# NNLightSwitcher_connectors.net
KiCad netlist of a schematic drawn in Altium Designer
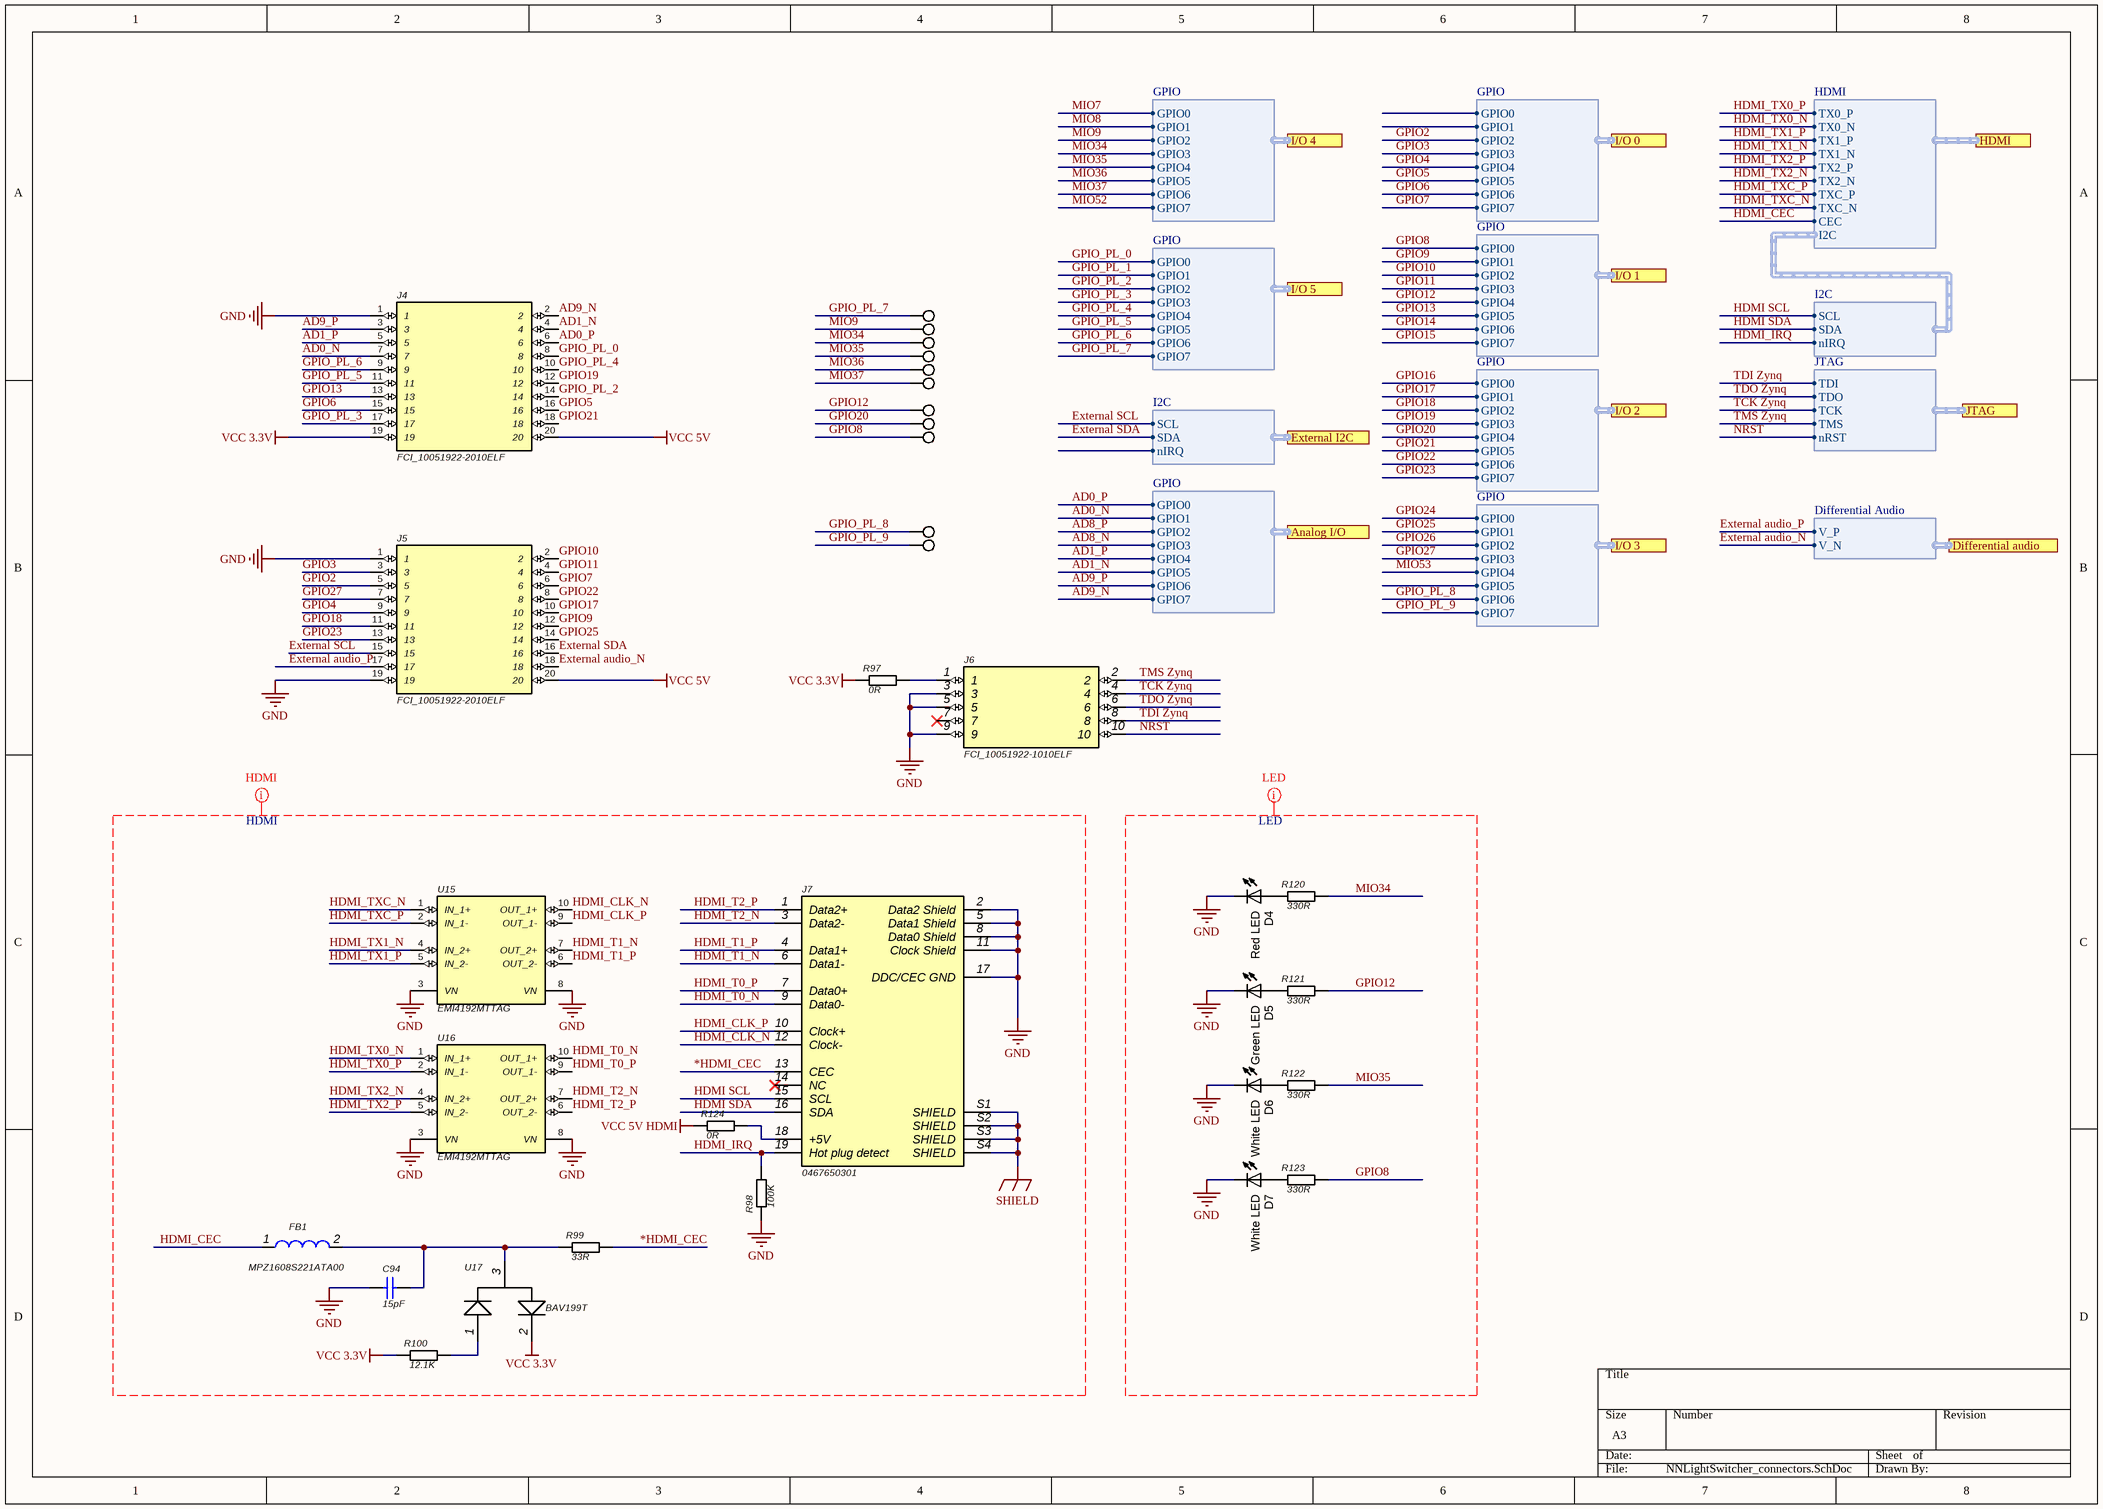
[diagram p0: NNLightSwitcher_connectors.SchDoc]

(export (version "E")
  (design (tool "Eeschema 10.0.6"))
  (components
    (comp (ref "C94")
      (value "15pF")
      (footprint "0402")
      (libsource (lib "NNLightSwitcher") (part "Capacitor 15pF"))
    )
    (comp (ref "D4")
      (value "Red LED")
      (footprint "*LED_SML-P11UTT86R_SML-P11MTT86(Primary)")
      (description "LED red 0402")
      (libsource (lib "NNLightSwitcher") (part "APHHS1005SURCK"))
    )
    (comp (ref "D5")
      (value "Green LED")
      (footprint "*LED_SML-P11UTT86R_SML-P11MTT86(Primary)")
      (description "LED Uni-Color Green 525nm 2-Pin Chip 0402_1006Metric_ T/RLT_VH9G-Q2OO-25-1")
      (libsource (lib "NNLightSwitcher") (part "LT_VH9G-Q2OO-25-1"))
    )
    (comp (ref "D6")
      (value "White LED")
      (footprint "*LED_SML-P11UTT86R_SML-P11MTT86(Primary)")
      (description "LED red 0402\r\nAPG1005RWF-T-5MAV")
      (libsource (lib "NNLightSwitcher") (part "APG1005RWF-T-5MAV"))
    )
    (comp (ref "D7")
      (value "White LED")
      (footprint "*LED_SML-P11UTT86R_SML-P11MTT86(Primary)")
      (description "LED red 0402\r\nAPG1005RWF-T-5MAV")
      (libsource (lib "NNLightSwitcher") (part "APG1005RWF-T-5MAV"))
    )
    (comp (ref "FB1")
      (value "MPZ1608S221ATA00")
      (footprint "*0603")
      (description "Ferrite Bead Multi-Layer 220Ohm 25% 100MHz Ferrite 2.2A 0603 Punched Paper T/R")
      (fields (field (name "TOLERANCE") "25%"))
      (libsource (lib "NNLightSwitcher") (part "MPZ1608S221ATA00"))
    )
    (comp (ref "J4")
      (value "FCI_10051922-2010ELF")
      (footprint "*FCI_10051922-2010ELF")
      (description "0.50mm FFC/FPC Connectors 20CKT RA SMT ZIF CON BOTTOM CONTACT")
      (libsource (lib "NNLightSwitcher") (part "FCI_10051922-2010ELF"))
    )
    (comp (ref "J5")
      (value "FCI_10051922-2010ELF")
      (footprint "*FCI_10051922-2010ELF")
      (description "0.50mm FFC/FPC Connectors 20CKT RA SMT ZIF CON BOTTOM CONTACT")
      (libsource (lib "NNLightSwitcher") (part "FCI_10051922-2010ELF"))
    )
    (comp (ref "J6")
      (value "FCI_10051922-1010ELF")
      (footprint "*FCI_10051922-1010ELF")
      (description "0.50mm FFC/FPC Connectors 10CKT RA SMT ZIF CON BOTTOM CONTACT")
      (libsource (lib "NNLightSwitcher") (part "FCI_10051922-1010ELF"))
    )
    (comp (ref "J7")
      (value "0467650301")
      (footprint "MOLEX_0467650301_0467650301(Primary)")
      (description "Conn Micro HDMI RCP 19 POS 0.4mm Solder RA SMD 19 Terminal 1 Port Micro HDMI Embossed T/R")
      (libsource (lib "NNLightSwitcher") (part "Micro HDMI"))
    )
    (comp (ref "R97")
      (value "0R")
      (footprint "0402")
      (libsource (lib "NNLightSwitcher") (part "Resistor 0R"))
    )
    (comp (ref "R98")
      (value "100K")
      (footprint "0402")
      (libsource (lib "NNLightSwitcher") (part "Resistor 100K"))
    )
    (comp (ref "R99")
      (value "33R")
      (footprint "0402")
      (libsource (lib "NNLightSwitcher") (part "Resistor 33R"))
    )
    (comp (ref "R100")
      (value "12.1K")
      (footprint "0402")
      (libsource (lib "NNLightSwitcher") (part "Resistor 12.1K"))
    )
    (comp (ref "R120")
      (value "330R")
      (footprint "0402")
      (libsource (lib "NNLightSwitcher") (part "Resistor 330R"))
    )
    (comp (ref "R121")
      (value "330R")
      (footprint "0402")
      (libsource (lib "NNLightSwitcher") (part "Resistor 330R"))
    )
    (comp (ref "R122")
      (value "330R")
      (footprint "0402")
      (libsource (lib "NNLightSwitcher") (part "Resistor 330R"))
    )
    (comp (ref "R123")
      (value "330R")
      (footprint "0402")
      (libsource (lib "NNLightSwitcher") (part "Resistor 330R"))
    )
    (comp (ref "R124")
      (value "0R")
      (footprint "0402")
      (libsource (lib "NNLightSwitcher") (part "Resistor 0R"))
    )
    (comp (ref "TP50")
      (value "Test point")
      (footprint "Testpoint_with_pad")
      (description "Test Point, Miniature, SMT")
      (libsource (lib "NNLightSwitcher") (part "Test point"))
    )
    (comp (ref "TP51")
      (value "Test point")
      (footprint "Testpoint_Keystone_Miniature")
      (description "Test Point, Miniature, SMT")
      (libsource (lib "NNLightSwitcher") (part "Test point"))
    )
    (comp (ref "TP52")
      (value "Test point")
      (footprint "Testpoint_Keystone_Miniature")
      (description "Test Point, Miniature, SMT")
      (libsource (lib "NNLightSwitcher") (part "Test point"))
    )
    (comp (ref "TP53")
      (value "Test point")
      (footprint "Testpoint_Keystone_Miniature")
      (description "Test Point, Miniature, SMT")
      (libsource (lib "NNLightSwitcher") (part "Test point"))
    )
    (comp (ref "TP54")
      (value "Test point")
      (footprint "Testpoint_Keystone_Miniature")
      (description "Test Point, Miniature, SMT")
      (libsource (lib "NNLightSwitcher") (part "Test point"))
    )
    (comp (ref "TP55")
      (value "Test point")
      (footprint "Testpoint_Keystone_Miniature")
      (description "Test Point, Miniature, SMT")
      (libsource (lib "NNLightSwitcher") (part "Test point"))
    )
    (comp (ref "TP63")
      (value "Test point")
      (footprint "Testpoint_with_pad")
      (description "Test Point, Miniature, SMT")
      (libsource (lib "NNLightSwitcher") (part "Test point"))
    )
    (comp (ref "TP64")
      (value "Test point")
      (footprint "Testpoint_with_pad")
      (description "Test Point, Miniature, SMT")
      (libsource (lib "NNLightSwitcher") (part "Test point"))
    )
    (comp (ref "TP65")
      (value "Test point")
      (footprint "Testpoint_with_pad")
      (description "Test Point, Miniature, SMT")
      (libsource (lib "NNLightSwitcher") (part "Test point"))
    )
    (comp (ref "TP67")
      (value "Test point")
      (footprint "Testpoint_with_pad")
      (description "Test Point, Miniature, SMT")
      (libsource (lib "NNLightSwitcher") (part "Test point"))
    )
    (comp (ref "TP70")
      (value "Test point")
      (footprint "Testpoint_with_pad")
      (description "Test Point, Miniature, SMT")
      (libsource (lib "NNLightSwitcher") (part "Test point"))
    )
    (comp (ref "U15")
      (value "EMI4192MTTAG")
      (footprint "ONSC-WDFN-10-511BM-01_V")
      (description "Common Mode Filter with ESD Protection, -40 to 85 degC, 10-Pin WDFN, Pb-Free, Tape and Reel")
      (libsource (lib "NNLightSwitcher") (part "EMI4192MTTAG"))
    )
    (comp (ref "U16")
      (value "EMI4192MTTAG")
      (footprint "ONSC-WDFN-10-511BM-01_V")
      (description "Common Mode Filter with ESD Protection, -40 to 85 degC, 10-Pin WDFN, Pb-Free, Tape and Reel")
      (libsource (lib "NNLightSwitcher") (part "EMI4192MTTAG"))
    )
    (comp (ref "U17")
      (value "BAV199T")
      (footprint "*SOT95P240X110-3N")
      (fields (field (name "MF") "Micro Commercial"))
      (libsource (lib "NNLightSwitcher") (part "BAV199T"))
    )
  )
  (nets
    (net (code "7") (name "/*HDMI_CEC") (class "Default")
      (node (ref "J7") (pin "13") (pinfunction "CEC_13") (pintype "passive"))
      (node (ref "R99") (pin "2") (pinfunction "2_2") (pintype "passive"))
    )
    (net (code "8") (name "/AD0_N") (class "Default")
      (node (ref "J4") (pin "7") (pinfunction "7_7") (pintype "bidirectional"))
    )
    (net (code "9") (name "/AD0_P") (class "Default")
      (node (ref "J4") (pin "6") (pinfunction "6_6") (pintype "bidirectional"))
    )
    (net (code "10") (name "/AD1_N") (class "Default")
      (node (ref "J4") (pin "4") (pinfunction "4_4") (pintype "bidirectional"))
    )
    (net (code "11") (name "/AD1_P") (class "Default")
      (node (ref "J4") (pin "5") (pinfunction "5_5") (pintype "bidirectional"))
    )
    (net (code "14") (name "/AD9_N") (class "Default")
      (node (ref "J4") (pin "2") (pinfunction "2_2") (pintype "bidirectional"))
    )
    (net (code "15") (name "/AD9_P") (class "Default")
      (node (ref "J4") (pin "3") (pinfunction "3_3") (pintype "bidirectional"))
    )
    (net (code "16") (name "/External SCL") (class "Default")
      (node (ref "J5") (pin "15") (pinfunction "15_15") (pintype "bidirectional"))
    )
    (net (code "17") (name "/External SDA") (class "Default")
      (node (ref "J5") (pin "16") (pinfunction "16_16") (pintype "bidirectional"))
    )
    (net (code "18") (name "/External audio_N") (class "Default")
      (node (ref "J5") (pin "18") (pinfunction "18_18") (pintype "bidirectional"))
    )
    (net (code "19") (name "/External audio_P") (class "Default")
      (node (ref "J5") (pin "17") (pinfunction "17_17") (pintype "bidirectional"))
    )
    (net (code "20") (name "/GPIO2") (class "Default")
      (node (ref "J5") (pin "5") (pinfunction "5_5") (pintype "bidirectional"))
    )
    (net (code "21") (name "/GPIO3") (class "Default")
      (node (ref "J5") (pin "3") (pinfunction "3_3") (pintype "bidirectional"))
    )
    (net (code "22") (name "/GPIO4") (class "Default")
      (node (ref "J5") (pin "9") (pinfunction "9_9") (pintype "bidirectional"))
    )
    (net (code "23") (name "/GPIO5") (class "Default")
      (node (ref "J4") (pin "16") (pinfunction "16_16") (pintype "bidirectional"))
    )
    (net (code "24") (name "/GPIO6") (class "Default")
      (node (ref "J4") (pin "15") (pinfunction "15_15") (pintype "bidirectional"))
    )
    (net (code "25") (name "/GPIO7") (class "Default")
      (node (ref "J5") (pin "6") (pinfunction "6_6") (pintype "bidirectional"))
    )
    (net (code "26") (name "/GPIO8") (class "Default")
      (node (ref "R123") (pin "2") (pinfunction "2_2") (pintype "passive"))
      (node (ref "TP65") (pin "1") (pintype "passive"))
    )
    (net (code "27") (name "/GPIO9") (class "Default")
      (node (ref "J5") (pin "12") (pinfunction "12_12") (pintype "bidirectional"))
    )
    (net (code "28") (name "/GPIO10") (class "Default")
      (node (ref "J5") (pin "2") (pinfunction "2_2") (pintype "bidirectional"))
    )
    (net (code "29") (name "/GPIO11") (class "Default")
      (node (ref "J5") (pin "4") (pinfunction "4_4") (pintype "bidirectional"))
    )
    (net (code "30") (name "/GPIO12") (class "Default")
      (node (ref "R121") (pin "2") (pinfunction "2_2") (pintype "passive"))
      (node (ref "TP63") (pin "1") (pintype "passive"))
    )
    (net (code "31") (name "/GPIO13") (class "Default")
      (node (ref "J4") (pin "13") (pinfunction "13_13") (pintype "bidirectional"))
    )
    (net (code "35") (name "/GPIO17") (class "Default")
      (node (ref "J5") (pin "10") (pinfunction "10_10") (pintype "bidirectional"))
    )
    (net (code "36") (name "/GPIO18") (class "Default")
      (node (ref "J5") (pin "11") (pinfunction "11_11") (pintype "bidirectional"))
    )
    (net (code "37") (name "/GPIO19") (class "Default")
      (node (ref "J4") (pin "12") (pinfunction "12_12") (pintype "bidirectional"))
    )
    (net (code "38") (name "/GPIO20") (class "Default") (node (ref "TP64") (pin "1") (pintype "passive")))
    (net (code "39") (name "/GPIO21") (class "Default")
      (node (ref "J4") (pin "18") (pinfunction "18_18") (pintype "bidirectional"))
    )
    (net (code "40") (name "/GPIO22") (class "Default")
      (node (ref "J5") (pin "8") (pinfunction "8_8") (pintype "bidirectional"))
    )
    (net (code "41") (name "/GPIO23") (class "Default")
      (node (ref "J5") (pin "13") (pinfunction "13_13") (pintype "bidirectional"))
    )
    (net (code "43") (name "/GPIO25") (class "Default")
      (node (ref "J5") (pin "14") (pinfunction "14_14") (pintype "bidirectional"))
    )
    (net (code "45") (name "/GPIO27") (class "Default")
      (node (ref "J5") (pin "7") (pinfunction "7_7") (pintype "bidirectional"))
    )
    (net (code "46") (name "/GPIO_PL_0") (class "Default")
      (node (ref "J4") (pin "8") (pinfunction "8_8") (pintype "bidirectional"))
    )
    (net (code "48") (name "/GPIO_PL_2") (class "Default")
      (node (ref "J4") (pin "14") (pinfunction "14_14") (pintype "bidirectional"))
    )
    (net (code "49") (name "/GPIO_PL_3") (class "Default")
      (node (ref "J4") (pin "17") (pinfunction "17_17") (pintype "bidirectional"))
    )
    (net (code "50") (name "/GPIO_PL_4") (class "Default")
      (node (ref "J4") (pin "10") (pinfunction "10_10") (pintype "bidirectional"))
    )
    (net (code "51") (name "/GPIO_PL_5") (class "Default")
      (node (ref "J4") (pin "11") (pinfunction "11_11") (pintype "bidirectional"))
    )
    (net (code "52") (name "/GPIO_PL_6") (class "Default")
      (node (ref "J4") (pin "9") (pinfunction "9_9") (pintype "bidirectional"))
    )
    (net (code "53") (name "/GPIO_PL_7") (class "Default") (node (ref "TP50") (pin "1") (pintype "passive")))
    (net (code "54") (name "/GPIO_PL_8") (class "Default") (node (ref "TP67") (pin "1") (pintype "passive")))
    (net (code "55") (name "/GPIO_PL_9") (class "Default") (node (ref "TP70") (pin "1") (pintype "passive")))
    (net (code "56") (name "/HDMI SCL") (class "Default")
      (node (ref "J7") (pin "15") (pinfunction "SCL_15") (pintype "passive"))
    )
    (net (code "57") (name "/HDMI SDA") (class "Default")
      (node (ref "J7") (pin "16") (pinfunction "SDA_16") (pintype "passive"))
    )
    (net (code "58") (name "/HDMI_CEC") (class "Default")
      (node (ref "FB1") (pin "1") (pinfunction "1_1") (pintype "passive"))
    )
    (net (code "59") (name "/HDMI_CLK_N") (class "Default")
      (node (ref "J7") (pin "12") (pinfunction "Clock-_12") (pintype "passive"))
      (node (ref "U15") (pin "10") (pinfunction "OUT_1+_10") (pintype "bidirectional"))
    )
    (net (code "60") (name "/HDMI_CLK_P") (class "Default")
      (node (ref "J7") (pin "10") (pinfunction "Clock+_10") (pintype "passive"))
      (node (ref "U15") (pin "9") (pinfunction "OUT_1-_9") (pintype "bidirectional"))
    )
    (net (code "61") (name "/HDMI_IRQ") (class "Default")
      (node (ref "J7") (pin "19") (pinfunction "Hot_plug_detect_19") (pintype "passive"))
      (node (ref "R98") (pin "2") (pinfunction "2_2") (pintype "passive"))
    )
    (net (code "62") (name "/HDMI_T0_N") (class "Default")
      (node (ref "J7") (pin "9") (pinfunction "Data0-_9") (pintype "passive"))
      (node (ref "U16") (pin "10") (pinfunction "OUT_1+_10") (pintype "bidirectional"))
    )
    (net (code "63") (name "/HDMI_T0_P") (class "Default")
      (node (ref "J7") (pin "7") (pinfunction "Data0+_7") (pintype "passive"))
      (node (ref "U16") (pin "9") (pinfunction "OUT_1-_9") (pintype "bidirectional"))
    )
    (net (code "64") (name "/HDMI_T1_N") (class "Default")
      (node (ref "J7") (pin "6") (pinfunction "Data1-_6") (pintype "passive"))
      (node (ref "U15") (pin "7") (pinfunction "OUT_2+_7") (pintype "bidirectional"))
    )
    (net (code "65") (name "/HDMI_T1_P") (class "Default")
      (node (ref "J7") (pin "4") (pinfunction "Data1+_4") (pintype "passive"))
      (node (ref "U15") (pin "6") (pinfunction "OUT_2-_6") (pintype "bidirectional"))
    )
    (net (code "66") (name "/HDMI_T2_N") (class "Default")
      (node (ref "J7") (pin "3") (pinfunction "Data2-_3") (pintype "passive"))
      (node (ref "U16") (pin "7") (pinfunction "OUT_2+_7") (pintype "bidirectional"))
    )
    (net (code "67") (name "/HDMI_T2_P") (class "Default")
      (node (ref "J7") (pin "1") (pinfunction "Data2+_1") (pintype "passive"))
      (node (ref "U16") (pin "6") (pinfunction "OUT_2-_6") (pintype "bidirectional"))
    )
    (net (code "68") (name "/HDMI_TX0_N") (class "Default")
      (node (ref "U16") (pin "1") (pinfunction "IN_1+_1") (pintype "bidirectional"))
    )
    (net (code "69") (name "/HDMI_TX0_P") (class "Default")
      (node (ref "U16") (pin "2") (pinfunction "IN_1-_2") (pintype "bidirectional"))
    )
    (net (code "70") (name "/HDMI_TX1_N") (class "Default")
      (node (ref "U15") (pin "4") (pinfunction "IN_2+_4") (pintype "bidirectional"))
    )
    (net (code "71") (name "/HDMI_TX1_P") (class "Default")
      (node (ref "U15") (pin "5") (pinfunction "IN_2-_5") (pintype "bidirectional"))
    )
    (net (code "72") (name "/HDMI_TX2_N") (class "Default")
      (node (ref "U16") (pin "4") (pinfunction "IN_2+_4") (pintype "bidirectional"))
    )
    (net (code "73") (name "/HDMI_TX2_P") (class "Default")
      (node (ref "U16") (pin "5") (pinfunction "IN_2-_5") (pintype "bidirectional"))
    )
    (net (code "74") (name "/HDMI_TXC_N") (class "Default")
      (node (ref "U15") (pin "1") (pinfunction "IN_1+_1") (pintype "bidirectional"))
    )
    (net (code "75") (name "/HDMI_TXC_P") (class "Default")
      (node (ref "U15") (pin "2") (pinfunction "IN_1-_2") (pintype "bidirectional"))
    )
    (net (code "78") (name "/MIO9") (class "Default") (node (ref "TP51") (pin "1") (pintype "passive")))
    (net (code "79") (name "/MIO34") (class "Default")
      (node (ref "R120") (pin "2") (pinfunction "2_2") (pintype "passive"))
      (node (ref "TP52") (pin "1") (pintype "passive"))
    )
    (net (code "80") (name "/MIO35") (class "Default")
      (node (ref "R122") (pin "2") (pinfunction "2_2") (pintype "passive"))
      (node (ref "TP53") (pin "1") (pintype "passive"))
    )
    (net (code "81") (name "/MIO36") (class "Default") (node (ref "TP54") (pin "1") (pintype "passive")))
    (net (code "82") (name "/MIO37") (class "Default") (node (ref "TP55") (pin "1") (pintype "passive")))
    (net (code "85") (name "/NRST") (class "Default")
      (node (ref "J6") (pin "10") (pinfunction "10_10") (pintype "bidirectional"))
    )
    (net (code "86") (name "/TCK Zynq") (class "Default")
      (node (ref "J6") (pin "4") (pinfunction "4_4") (pintype "bidirectional"))
    )
    (net (code "87") (name "/TDI Zynq") (class "Default")
      (node (ref "J6") (pin "8") (pinfunction "8_8") (pintype "bidirectional"))
    )
    (net (code "88") (name "/TDO Zynq") (class "Default")
      (node (ref "J6") (pin "6") (pinfunction "6_6") (pintype "bidirectional"))
    )
    (net (code "89") (name "/TMS Zynq") (class "Default")
      (node (ref "J6") (pin "2") (pinfunction "2_2") (pintype "bidirectional"))
    )
    (net (code "95") (name "GND") (class "Default")
      (node (ref "C94") (pin "2") (pinfunction "2_2") (pintype "passive"))
      (node (ref "D4") (pin "C") (pinfunction "C_C") (pintype "passive"))
      (node (ref "D5") (pin "C") (pinfunction "C_C") (pintype "passive"))
      (node (ref "D6") (pin "C") (pinfunction "C_C") (pintype "passive"))
      (node (ref "D7") (pin "C") (pinfunction "C_C") (pintype "passive"))
      (node (ref "J4") (pin "1") (pinfunction "1_1") (pintype "bidirectional"))
      (node (ref "J5") (pin "1") (pinfunction "1_1") (pintype "bidirectional"))
      (node (ref "J5") (pin "19") (pinfunction "19_19") (pintype "bidirectional"))
      (node (ref "J6") (pin "3") (pinfunction "3_3") (pintype "bidirectional"))
      (node (ref "J6") (pin "5") (pinfunction "5_5") (pintype "bidirectional"))
      (node (ref "J6") (pin "9") (pinfunction "9_9") (pintype "bidirectional"))
      (node (ref "J7") (pin "11") (pinfunction "Clock_Shield_11") (pintype "passive"))
      (node (ref "J7") (pin "17") (pinfunction "DDC/CEC_GND_17") (pintype "passive"))
      (node (ref "J7") (pin "2") (pinfunction "Data2_Shield_2") (pintype "passive"))
      (node (ref "J7") (pin "5") (pinfunction "Data1_Shield_5") (pintype "passive"))
      (node (ref "J7") (pin "8") (pinfunction "Data0_Shield_8") (pintype "passive"))
      (node (ref "R98") (pin "1") (pinfunction "1_1") (pintype "passive"))
      (node (ref "U15") (pin "3") (pinfunction "VN_3") (pintype "power_in"))
      (node (ref "U15") (pin "8") (pinfunction "VN_8") (pintype "power_in"))
      (node (ref "U16") (pin "3") (pinfunction "VN_3") (pintype "power_in"))
      (node (ref "U16") (pin "8") (pinfunction "VN_8") (pintype "power_in"))
    )
    (net (code "96") (name "Net-(D4-PadA)") (class "Default")
      (node (ref "D4") (pin "A") (pinfunction "A_A") (pintype "passive"))
      (node (ref "R120") (pin "1") (pinfunction "1_1") (pintype "passive"))
    )
    (net (code "97") (name "Net-(D5-PadA)") (class "Default")
      (node (ref "D5") (pin "A") (pinfunction "A_A") (pintype "passive"))
      (node (ref "R121") (pin "1") (pinfunction "1_1") (pintype "passive"))
    )
    (net (code "98") (name "Net-(D6-PadA)") (class "Default")
      (node (ref "D6") (pin "A") (pinfunction "A_A") (pintype "passive"))
      (node (ref "R122") (pin "1") (pinfunction "1_1") (pintype "passive"))
    )
    (net (code "99") (name "Net-(D7-PadA)") (class "Default")
      (node (ref "D7") (pin "A") (pinfunction "A_A") (pintype "passive"))
      (node (ref "R123") (pin "1") (pinfunction "1_1") (pintype "passive"))
    )
    (net (code "100") (name "Net-(J6-Pad1)") (class "Default")
      (node (ref "J6") (pin "1") (pinfunction "1_1") (pintype "bidirectional"))
      (node (ref "R97") (pin "2") (pinfunction "2_2") (pintype "passive"))
    )
    (net (code "101") (name "Net-(J7-+5V)") (class "Default")
      (node (ref "J7") (pin "18") (pinfunction "+5V_18") (pintype "passive"))
      (node (ref "R124") (pin "2") (pinfunction "2_2") (pintype "passive"))
    )
    (net (code "102") (name "Net-(U17-ANODE)") (class "Default")
      (node (ref "R100") (pin "2") (pinfunction "2_2") (pintype "passive"))
      (node (ref "U17") (pin "1") (pinfunction "ANODE_1") (pintype "passive"))
    )
    (net (code "103") (name "Net-(U17-ANODE{slash}CATHODE)") (class "Default")
      (node (ref "C94") (pin "1") (pinfunction "1_1") (pintype "passive"))
      (node (ref "FB1") (pin "2") (pinfunction "2_2") (pintype "passive"))
      (node (ref "R99") (pin "1") (pinfunction "1_1") (pintype "passive"))
      (node (ref "U17") (pin "3") (pinfunction "ANODE/CATHODE_3") (pintype "passive"))
    )
    (net (code "104") (name "SHIELD") (class "Default")
      (node (ref "J7") (pin "S1") (pinfunction "SHIELD_S1") (pintype "passive"))
      (node (ref "J7") (pin "S2") (pinfunction "SHIELD_S2") (pintype "passive"))
      (node (ref "J7") (pin "S3") (pinfunction "SHIELD_S3") (pintype "passive"))
      (node (ref "J7") (pin "S4") (pinfunction "SHIELD_S4") (pintype "passive"))
    )
    (net (code "105") (name "VCC 3.3V") (class "Default")
      (node (ref "J4") (pin "19") (pinfunction "19_19") (pintype "bidirectional"))
      (node (ref "R100") (pin "1") (pinfunction "1_1") (pintype "passive"))
      (node (ref "R97") (pin "1") (pinfunction "1_1") (pintype "passive"))
      (node (ref "U17") (pin "2") (pinfunction "CATHODE_2") (pintype "passive"))
    )
    (net (code "106") (name "VCC 5V") (class "Default")
      (node (ref "J4") (pin "20") (pinfunction "20_20") (pintype "bidirectional"))
      (node (ref "J5") (pin "20") (pinfunction "20_20") (pintype "bidirectional"))
    )
    (net (code "107") (name "VCC 5V HDMI") (class "Default")
      (node (ref "R124") (pin "1") (pinfunction "1_1") (pintype "passive"))
    )
    (net (code "108") (name "unconnected-(J6-Pad7)") (class "Default")
      (node (ref "J6") (pin "7") (pinfunction "7_7") (pintype "bidirectional+no_connect"))
    )
    (net (code "109") (name "unconnected-(J7-NC-Pad14)") (class "Default")
      (node (ref "J7") (pin "14") (pinfunction "NC_14") (pintype "passive+no_connect"))
    )
  )
)
